# Analog_Sensors_Sheet.net
KiCad netlist of a schematic drawn in Altium Designer
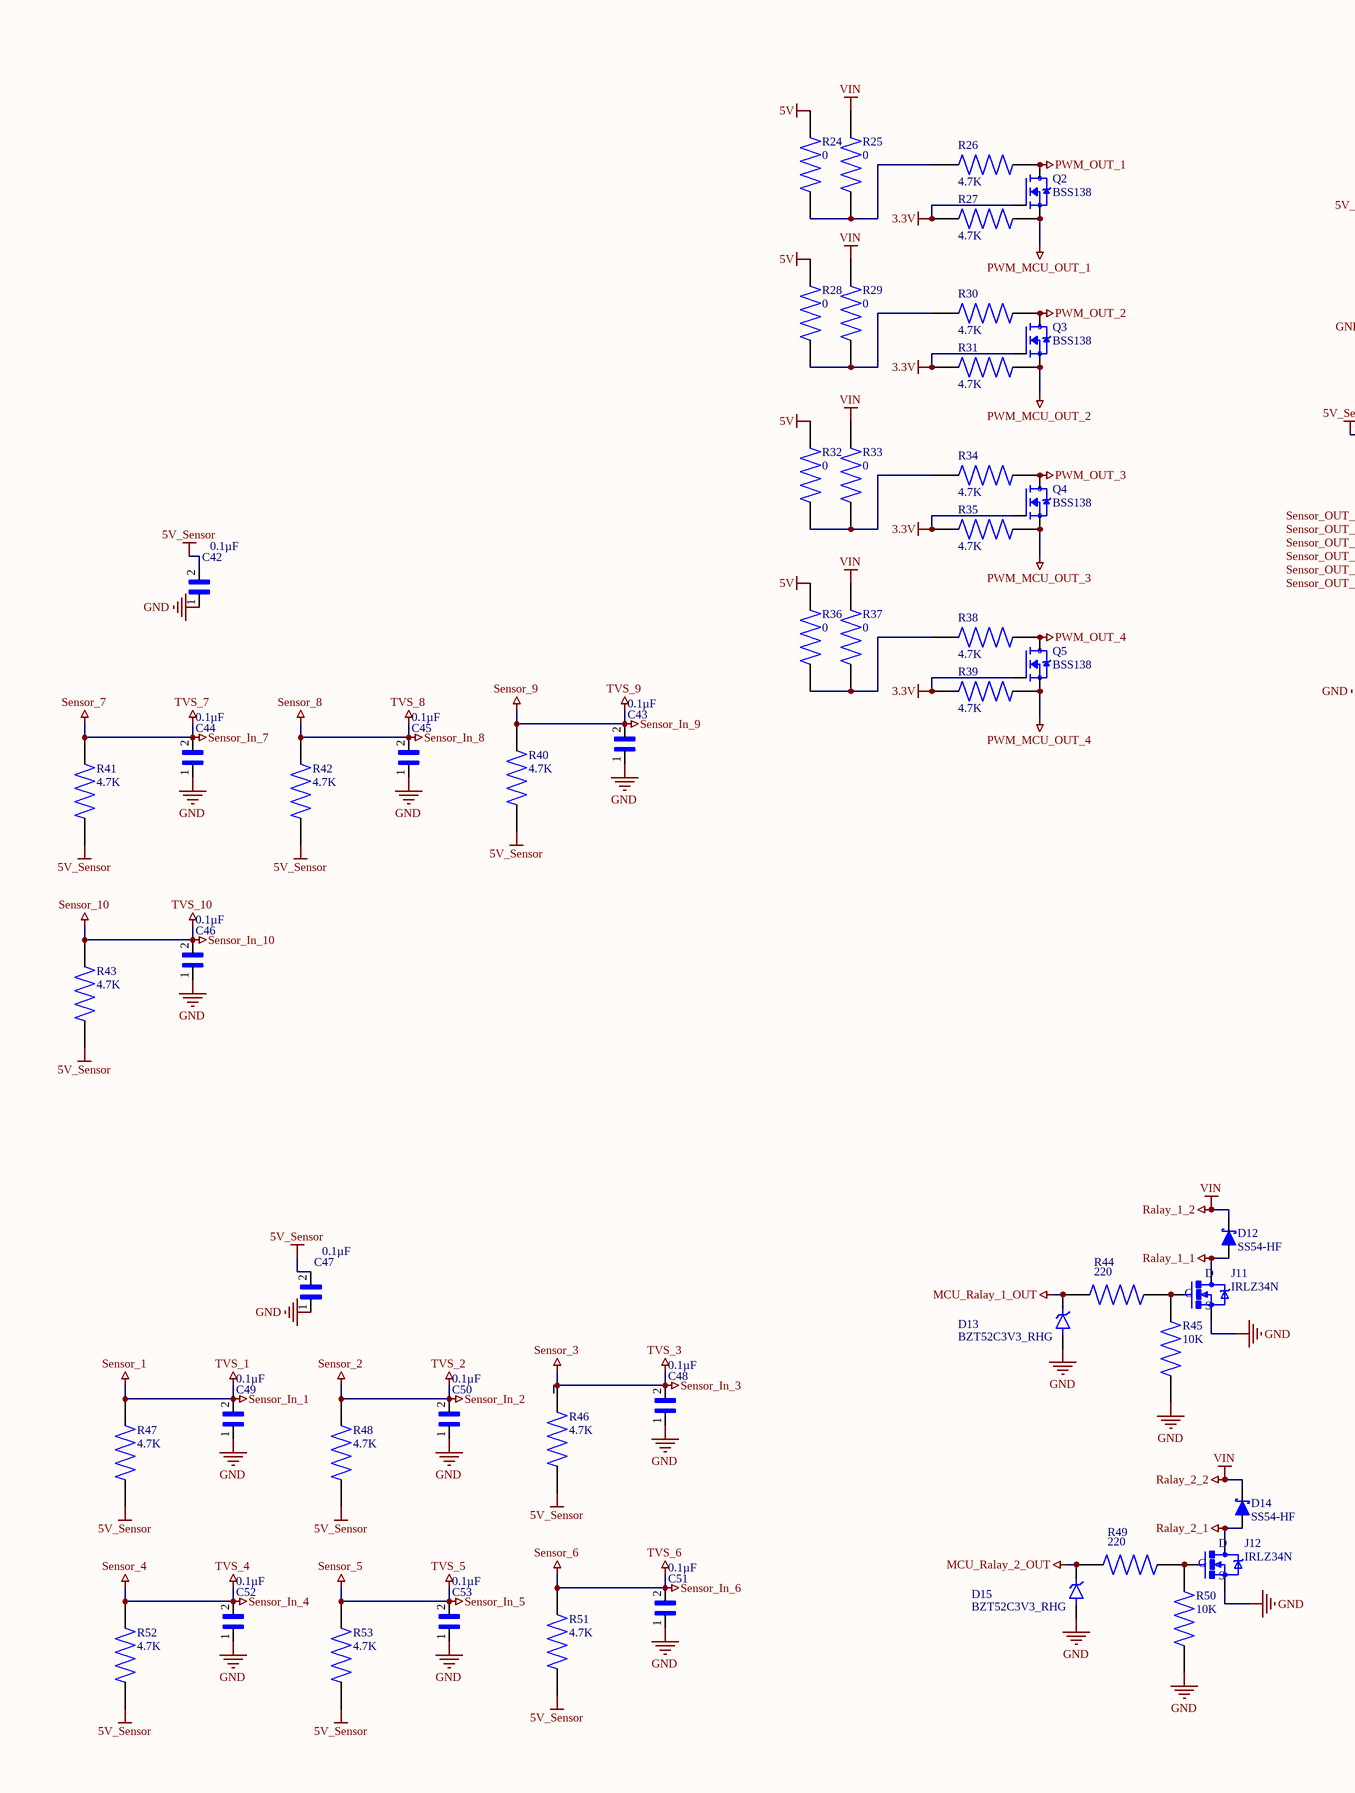
[diagram p0: Analog_Sensors_Sheet.SchDoc, left]
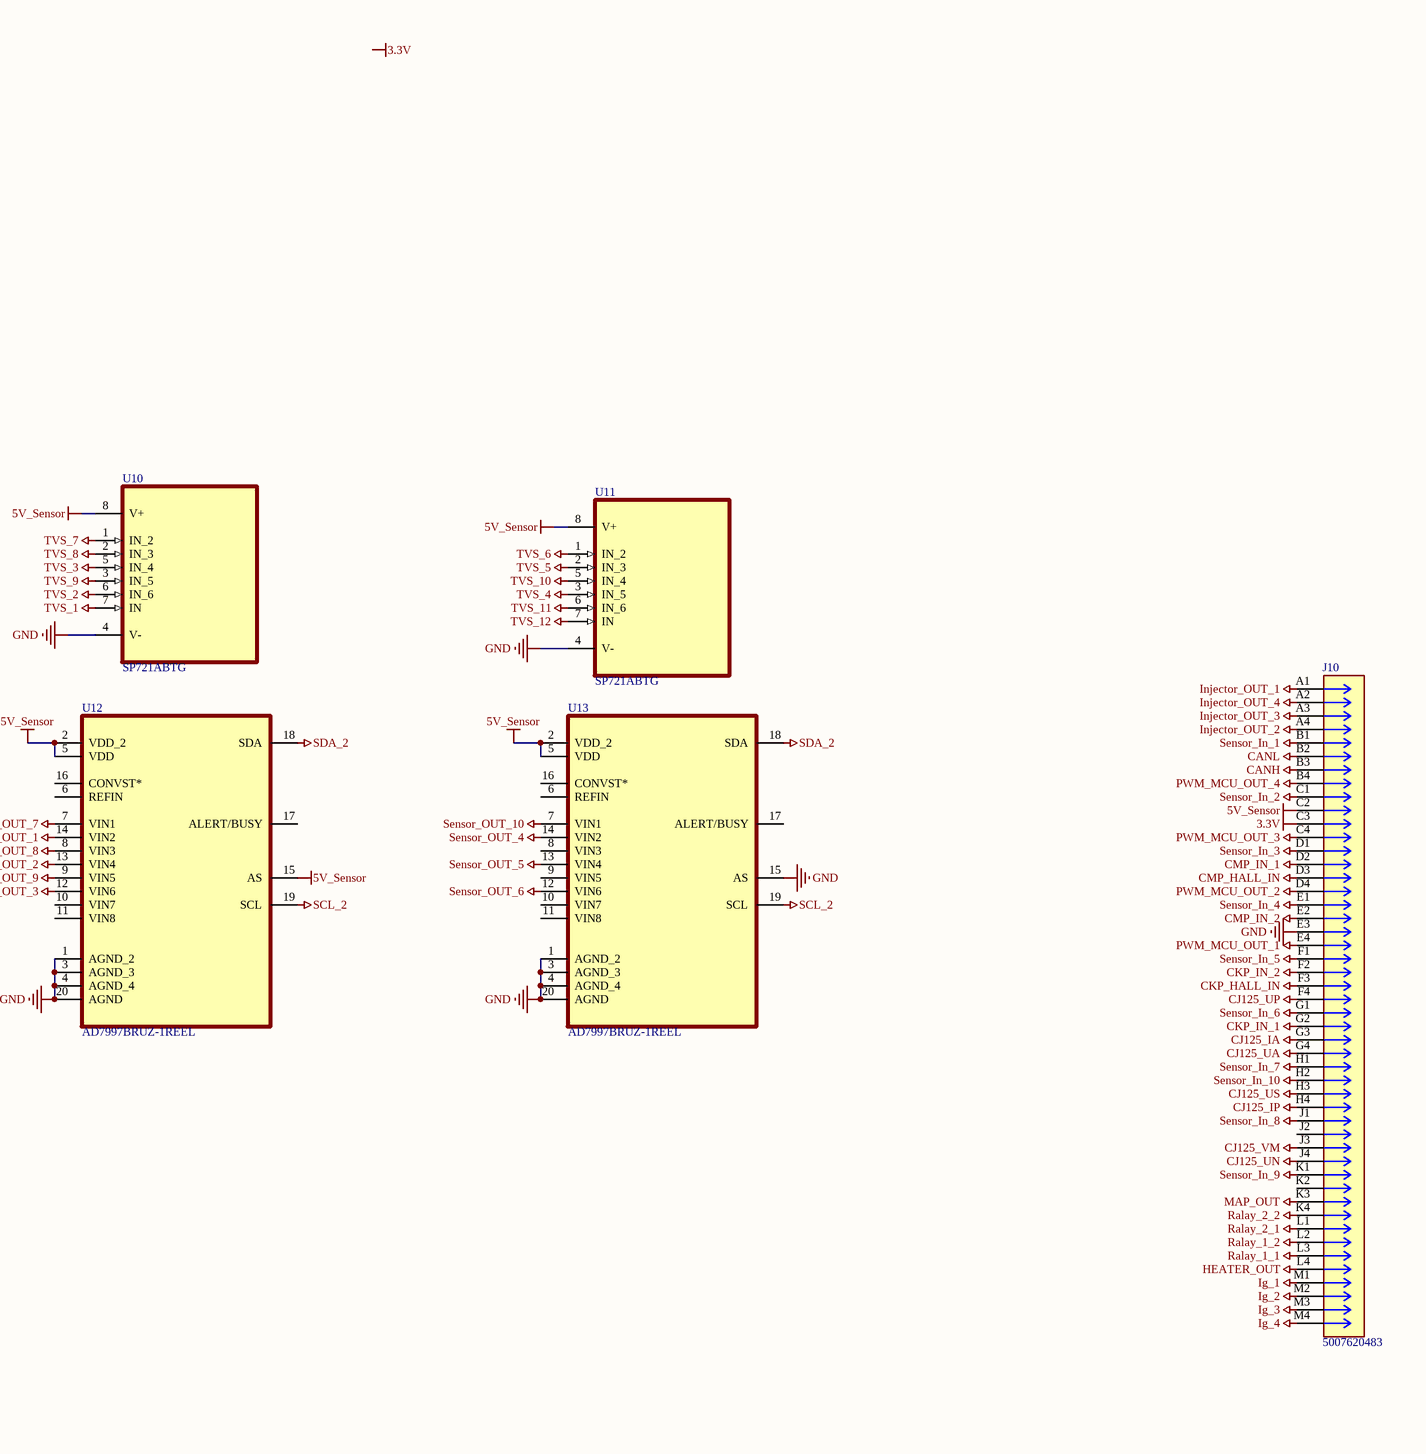
[diagram p1: Analog_Sensors_Sheet.SchDoc, right]

(export (version "E")
  (design (tool "Eeschema 10.0.6"))
  (components
    (comp (ref "C42")
      (value "0.1µF")
      (footprint "CAPC1608X90N")
      (description "Multilayer Ceramic Capacitors MLCC - SMD/SMT")
      (fields (field (name "MP") "06035C104MAZ2A"))
      (libsource (lib "06035C104MAZ2A") (part "06035C104MAZ2A"))
    )
    (comp (ref "C43")
      (value "0.1µF")
      (footprint "CAPC1608X90N")
      (description "Multilayer Ceramic Capacitors MLCC - SMD/SMT")
      (fields (field (name "MP") "06035C104MAZ2A"))
      (libsource (lib "06035C104MAZ2A") (part "06035C104MAZ2A"))
    )
    (comp (ref "C44")
      (value "0.1µF")
      (footprint "CAPC1608X90N")
      (description "Multilayer Ceramic Capacitors MLCC - SMD/SMT")
      (fields (field (name "MP") "06035C104MAZ2A"))
      (libsource (lib "06035C104MAZ2A") (part "06035C104MAZ2A"))
    )
    (comp (ref "C45")
      (value "0.1µF")
      (footprint "CAPC1608X90N")
      (description "Multilayer Ceramic Capacitors MLCC - SMD/SMT")
      (fields (field (name "MP") "06035C104MAZ2A"))
      (libsource (lib "06035C104MAZ2A") (part "06035C104MAZ2A"))
    )
    (comp (ref "C46")
      (value "0.1µF")
      (footprint "CAPC1608X90N")
      (description "Multilayer Ceramic Capacitors MLCC - SMD/SMT")
      (fields (field (name "MP") "06035C104MAZ2A"))
      (libsource (lib "06035C104MAZ2A") (part "06035C104MAZ2A"))
    )
    (comp (ref "C47")
      (value "0.1µF")
      (footprint "CAPC1608X90N")
      (description "Multilayer Ceramic Capacitors MLCC - SMD/SMT")
      (fields (field (name "MP") "06035C104MAZ2A"))
      (libsource (lib "06035C104MAZ2A") (part "06035C104MAZ2A"))
    )
    (comp (ref "C48")
      (value "0.1µF")
      (footprint "CAPC1608X90N")
      (description "Multilayer Ceramic Capacitors MLCC - SMD/SMT")
      (fields (field (name "MP") "06035C104MAZ2A"))
      (libsource (lib "06035C104MAZ2A") (part "06035C104MAZ2A"))
    )
    (comp (ref "C49")
      (value "0.1µF")
      (footprint "CAPC1608X90N")
      (description "Multilayer Ceramic Capacitors MLCC - SMD/SMT")
      (fields (field (name "MP") "06035C104MAZ2A"))
      (libsource (lib "06035C104MAZ2A") (part "06035C104MAZ2A"))
    )
    (comp (ref "C50")
      (value "0.1µF")
      (footprint "CAPC1608X90N")
      (description "Multilayer Ceramic Capacitors MLCC - SMD/SMT")
      (fields (field (name "MP") "06035C104MAZ2A"))
      (libsource (lib "06035C104MAZ2A") (part "06035C104MAZ2A"))
    )
    (comp (ref "C51")
      (value "0.1µF")
      (footprint "CAPC1608X90N")
      (description "Multilayer Ceramic Capacitors MLCC - SMD/SMT")
      (fields (field (name "MP") "06035C104MAZ2A"))
      (libsource (lib "06035C104MAZ2A") (part "06035C104MAZ2A"))
    )
    (comp (ref "C52")
      (value "0.1µF")
      (footprint "CAPC1608X90N")
      (description "Multilayer Ceramic Capacitors MLCC - SMD/SMT")
      (fields (field (name "MP") "06035C104MAZ2A"))
      (libsource (lib "06035C104MAZ2A") (part "06035C104MAZ2A"))
    )
    (comp (ref "C53")
      (value "0.1µF")
      (footprint "CAPC1608X90N")
      (description "Multilayer Ceramic Capacitors MLCC - SMD/SMT")
      (fields (field (name "MP") "06035C104MAZ2A"))
      (libsource (lib "06035C104MAZ2A") (part "06035C104MAZ2A"))
    )
    (comp (ref "D12")
      (value "SS54-HF")
      (footprint "DIOM5025X220N")
      (description "Diode Schottky 40 V 5A Surface Mount DO-214AC (SMA)")
      (fields (field (name "MF") "Comchip Technology"))
      (libsource (lib "SS54-HF") (part "SS54-HF"))
    )
    (comp (ref "D13")
      (value "BZT52C3V3_RHG")
      (footprint "DIO_BZT52C3V3_RHG")
      (libsource (lib "BZT52C3V3_RHG") (part "BZT52C3V3_RHG"))
    )
    (comp (ref "D14")
      (value "SS54-HF")
      (footprint "DIOM5025X220N")
      (description "Diode Schottky 40 V 5A Surface Mount DO-214AC (SMA)")
      (fields (field (name "MF") "Comchip Technology"))
      (libsource (lib "SS54-HF") (part "SS54-HF"))
    )
    (comp (ref "D15")
      (value "BZT52C3V3_RHG")
      (footprint "DIO_BZT52C3V3_RHG")
      (libsource (lib "BZT52C3V3_RHG") (part "BZT52C3V3_RHG"))
    )
    (comp (ref "J10")
      (value "5007620483")
      (footprint "CONN_SD-500762-001_MOL")
      (libsource (lib "5007620483") (part "5007620483"))
    )
    (comp (ref "J11")
      (value "IRLZ34N")
      (footprint "TO-220(2)")
      (description "N-Channel 55 V 30A (Tc) 3.8W (Ta), 68W (Tc) Surface Mount D2PAK")
      (fields (field (name "MF") "Infineon"))
      (libsource (lib "IRLZ34N") (part "IRLZ34N"))
    )
    (comp (ref "J12")
      (value "IRLZ34N")
      (footprint "TO-220(2)")
      (description "N-Channel 55 V 30A (Tc) 3.8W (Ta), 68W (Tc) Surface Mount D2PAK")
      (fields (field (name "MF") "Infineon"))
      (libsource (lib "IRLZ34N") (part "IRLZ34N"))
    )
    (comp (ref "Q2")
      (value "BSS138")
      (footprint "SOT95P240X111-3N")
      (description "N-Channel 50 V 220mA (Ta) 350mW (Ta) Surface Mount SOT-23-3")
      (fields (field (name "MF") "onsemi"))
      (libsource (lib "BSS138") (part "BSS138"))
    )
    (comp (ref "Q3")
      (value "BSS138")
      (footprint "SOT95P240X111-3N")
      (description "N-Channel 50 V 220mA (Ta) 350mW (Ta) Surface Mount SOT-23-3")
      (fields (field (name "MF") "onsemi"))
      (libsource (lib "BSS138") (part "BSS138"))
    )
    (comp (ref "Q4")
      (value "BSS138")
      (footprint "SOT95P240X111-3N")
      (description "N-Channel 50 V 220mA (Ta) 350mW (Ta) Surface Mount SOT-23-3")
      (fields (field (name "MF") "onsemi"))
      (libsource (lib "BSS138") (part "BSS138"))
    )
    (comp (ref "Q5")
      (value "BSS138")
      (footprint "SOT95P240X111-3N")
      (description "N-Channel 50 V 220mA (Ta) 350mW (Ta) Surface Mount SOT-23-3")
      (fields (field (name "MF") "onsemi"))
      (libsource (lib "BSS138") (part "BSS138"))
    )
    (comp (ref "R24")
      (value "0")
      (footprint "RESC3116X65N")
      (description "4.7 kOhms Â±1% 0.25W, 1/4W Chip Resistor 1206 (3216 Metric) Moisture Resistant Thick Film")
      (fields (field (name "MF") "Yageo") (field (name "MP") "RC1206FR-074K7L"))
      (libsource (lib "RC1206FR-074K7L") (part "RC1206FR-074K7L"))
    )
    (comp (ref "R25")
      (value "0")
      (footprint "RESC3116X65N")
      (description "4.7 kOhms Â±1% 0.25W, 1/4W Chip Resistor 1206 (3216 Metric) Moisture Resistant Thick Film")
      (fields (field (name "MF") "Yageo") (field (name "MP") "RC1206FR-074K7L"))
      (libsource (lib "RC1206FR-074K7L") (part "RC1206FR-074K7L"))
    )
    (comp (ref "R26")
      (value "4.7K")
      (footprint "RESC3116X65N")
      (description "4.7 kOhms Â±1% 0.25W, 1/4W Chip Resistor 1206 (3216 Metric) Moisture Resistant Thick Film")
      (fields (field (name "MF") "Yageo") (field (name "MP") "RC1206FR-074K7L"))
      (libsource (lib "RC1206FR-074K7L") (part "RC1206FR-074K7L"))
    )
    (comp (ref "R27")
      (value "4.7K")
      (footprint "RESC3116X65N")
      (description "4.7 kOhms Â±1% 0.25W, 1/4W Chip Resistor 1206 (3216 Metric) Moisture Resistant Thick Film")
      (fields (field (name "MF") "Yageo") (field (name "MP") "RC1206FR-074K7L"))
      (libsource (lib "RC1206FR-074K7L") (part "RC1206FR-074K7L"))
    )
    (comp (ref "R28")
      (value "0")
      (footprint "RESC3116X65N")
      (description "4.7 kOhms Â±1% 0.25W, 1/4W Chip Resistor 1206 (3216 Metric) Moisture Resistant Thick Film")
      (fields (field (name "MF") "Yageo") (field (name "MP") "RC1206FR-074K7L"))
      (libsource (lib "RC1206FR-074K7L") (part "RC1206FR-074K7L"))
    )
    (comp (ref "R29")
      (value "0")
      (footprint "RESC3116X65N")
      (description "4.7 kOhms Â±1% 0.25W, 1/4W Chip Resistor 1206 (3216 Metric) Moisture Resistant Thick Film")
      (fields (field (name "MF") "Yageo") (field (name "MP") "RC1206FR-074K7L"))
      (libsource (lib "RC1206FR-074K7L") (part "RC1206FR-074K7L"))
    )
    (comp (ref "R30")
      (value "4.7K")
      (footprint "RESC3116X65N")
      (description "4.7 kOhms Â±1% 0.25W, 1/4W Chip Resistor 1206 (3216 Metric) Moisture Resistant Thick Film")
      (fields (field (name "MF") "Yageo") (field (name "MP") "RC1206FR-074K7L"))
      (libsource (lib "RC1206FR-074K7L") (part "RC1206FR-074K7L"))
    )
    (comp (ref "R31")
      (value "4.7K")
      (footprint "RESC3116X65N")
      (description "4.7 kOhms Â±1% 0.25W, 1/4W Chip Resistor 1206 (3216 Metric) Moisture Resistant Thick Film")
      (fields (field (name "MF") "Yageo") (field (name "MP") "RC1206FR-074K7L"))
      (libsource (lib "RC1206FR-074K7L") (part "RC1206FR-074K7L"))
    )
    (comp (ref "R32")
      (value "0")
      (footprint "RESC3116X65N")
      (description "4.7 kOhms Â±1% 0.25W, 1/4W Chip Resistor 1206 (3216 Metric) Moisture Resistant Thick Film")
      (fields (field (name "MF") "Yageo") (field (name "MP") "RC1206FR-074K7L"))
      (libsource (lib "RC1206FR-074K7L") (part "RC1206FR-074K7L"))
    )
    (comp (ref "R33")
      (value "0")
      (footprint "RESC3116X65N")
      (description "4.7 kOhms Â±1% 0.25W, 1/4W Chip Resistor 1206 (3216 Metric) Moisture Resistant Thick Film")
      (fields (field (name "MF") "Yageo") (field (name "MP") "RC1206FR-074K7L"))
      (libsource (lib "RC1206FR-074K7L") (part "RC1206FR-074K7L"))
    )
    (comp (ref "R34")
      (value "4.7K")
      (footprint "RESC3116X65N")
      (description "4.7 kOhms Â±1% 0.25W, 1/4W Chip Resistor 1206 (3216 Metric) Moisture Resistant Thick Film")
      (fields (field (name "MF") "Yageo") (field (name "MP") "RC1206FR-074K7L"))
      (libsource (lib "RC1206FR-074K7L") (part "RC1206FR-074K7L"))
    )
    (comp (ref "R35")
      (value "4.7K")
      (footprint "RESC3116X65N")
      (description "4.7 kOhms Â±1% 0.25W, 1/4W Chip Resistor 1206 (3216 Metric) Moisture Resistant Thick Film")
      (fields (field (name "MF") "Yageo") (field (name "MP") "RC1206FR-074K7L"))
      (libsource (lib "RC1206FR-074K7L") (part "RC1206FR-074K7L"))
    )
    (comp (ref "R36")
      (value "0")
      (footprint "RESC3116X65N")
      (description "4.7 kOhms Â±1% 0.25W, 1/4W Chip Resistor 1206 (3216 Metric) Moisture Resistant Thick Film")
      (fields (field (name "MF") "Yageo") (field (name "MP") "RC1206FR-074K7L"))
      (libsource (lib "RC1206FR-074K7L") (part "RC1206FR-074K7L"))
    )
    (comp (ref "R37")
      (value "0")
      (footprint "RESC3116X65N")
      (description "4.7 kOhms Â±1% 0.25W, 1/4W Chip Resistor 1206 (3216 Metric) Moisture Resistant Thick Film")
      (fields (field (name "MF") "Yageo") (field (name "MP") "RC1206FR-074K7L"))
      (libsource (lib "RC1206FR-074K7L") (part "RC1206FR-074K7L"))
    )
    (comp (ref "R38")
      (value "4.7K")
      (footprint "RESC3116X65N")
      (description "4.7 kOhms Â±1% 0.25W, 1/4W Chip Resistor 1206 (3216 Metric) Moisture Resistant Thick Film")
      (fields (field (name "MF") "Yageo") (field (name "MP") "RC1206FR-074K7L"))
      (libsource (lib "RC1206FR-074K7L") (part "RC1206FR-074K7L"))
    )
    (comp (ref "R39")
      (value "4.7K")
      (footprint "RESC3116X65N")
      (description "4.7 kOhms Â±1% 0.25W, 1/4W Chip Resistor 1206 (3216 Metric) Moisture Resistant Thick Film")
      (fields (field (name "MF") "Yageo") (field (name "MP") "RC1206FR-074K7L"))
      (libsource (lib "RC1206FR-074K7L") (part "RC1206FR-074K7L"))
    )
    (comp (ref "R40")
      (value "4.7K")
      (footprint "RESC3116X65N")
      (description "4.7 kOhms Â±1% 0.25W, 1/4W Chip Resistor 1206 (3216 Metric) Moisture Resistant Thick Film")
      (fields (field (name "MF") "Yageo") (field (name "MP") "RC1206FR-074K7L"))
      (libsource (lib "RC1206FR-074K7L") (part "RC1206FR-074K7L"))
    )
    (comp (ref "R41")
      (value "4.7K")
      (footprint "RESC3116X65N")
      (description "4.7 kOhms Â±1% 0.25W, 1/4W Chip Resistor 1206 (3216 Metric) Moisture Resistant Thick Film")
      (fields (field (name "MF") "Yageo") (field (name "MP") "RC1206FR-074K7L"))
      (libsource (lib "RC1206FR-074K7L") (part "RC1206FR-074K7L"))
    )
    (comp (ref "R42")
      (value "4.7K")
      (footprint "RESC3116X65N")
      (description "4.7 kOhms Â±1% 0.25W, 1/4W Chip Resistor 1206 (3216 Metric) Moisture Resistant Thick Film")
      (fields (field (name "MF") "Yageo") (field (name "MP") "RC1206FR-074K7L"))
      (libsource (lib "RC1206FR-074K7L") (part "RC1206FR-074K7L"))
    )
    (comp (ref "R43")
      (value "4.7K")
      (footprint "RESC3116X65N")
      (description "4.7 kOhms Â±1% 0.25W, 1/4W Chip Resistor 1206 (3216 Metric) Moisture Resistant Thick Film")
      (fields (field (name "MF") "Yageo") (field (name "MP") "RC1206FR-074K7L"))
      (libsource (lib "RC1206FR-074K7L") (part "RC1206FR-074K7L"))
    )
    (comp (ref "R44")
      (value "220")
      (footprint "RESC3116X65N")
      (fields (field (name "MP") "AA1206JR-07470RL"))
      (libsource (lib "AA1206JR-07470RL") (part "AA1206JR-07470RL"))
    )
    (comp (ref "R45")
      (value "10K")
      (footprint "RESC3116X65N")
      (fields (field (name "MP") "AA1206JR-07470RL"))
      (libsource (lib "AA1206JR-07470RL") (part "AA1206JR-07470RL"))
    )
    (comp (ref "R46")
      (value "4.7K")
      (footprint "RESC3116X65N")
      (description "4.7 kOhms Â±1% 0.25W, 1/4W Chip Resistor 1206 (3216 Metric) Moisture Resistant Thick Film")
      (fields (field (name "MF") "Yageo") (field (name "MP") "RC1206FR-074K7L"))
      (libsource (lib "RC1206FR-074K7L") (part "RC1206FR-074K7L"))
    )
    (comp (ref "R47")
      (value "4.7K")
      (footprint "RESC3116X65N")
      (description "4.7 kOhms Â±1% 0.25W, 1/4W Chip Resistor 1206 (3216 Metric) Moisture Resistant Thick Film")
      (fields (field (name "MF") "Yageo") (field (name "MP") "RC1206FR-074K7L"))
      (libsource (lib "RC1206FR-074K7L") (part "RC1206FR-074K7L"))
    )
    (comp (ref "R48")
      (value "4.7K")
      (footprint "RESC3116X65N")
      (description "4.7 kOhms Â±1% 0.25W, 1/4W Chip Resistor 1206 (3216 Metric) Moisture Resistant Thick Film")
      (fields (field (name "MF") "Yageo") (field (name "MP") "RC1206FR-074K7L"))
      (libsource (lib "RC1206FR-074K7L") (part "RC1206FR-074K7L"))
    )
    (comp (ref "R49")
      (value "220")
      (footprint "RESC3116X65N")
      (fields (field (name "MP") "AA1206JR-07470RL"))
      (libsource (lib "AA1206JR-07470RL") (part "AA1206JR-07470RL"))
    )
    (comp (ref "R50")
      (value "10K")
      (footprint "RESC3116X65N")
      (fields (field (name "MP") "AA1206JR-07470RL"))
      (libsource (lib "AA1206JR-07470RL") (part "AA1206JR-07470RL"))
    )
    (comp (ref "R51")
      (value "4.7K")
      (footprint "RESC3116X65N")
      (description "4.7 kOhms Â±1% 0.25W, 1/4W Chip Resistor 1206 (3216 Metric) Moisture Resistant Thick Film")
      (fields (field (name "MF") "Yageo") (field (name "MP") "RC1206FR-074K7L"))
      (libsource (lib "RC1206FR-074K7L") (part "RC1206FR-074K7L"))
    )
    (comp (ref "R52")
      (value "4.7K")
      (footprint "RESC3116X65N")
      (description "4.7 kOhms Â±1% 0.25W, 1/4W Chip Resistor 1206 (3216 Metric) Moisture Resistant Thick Film")
      (fields (field (name "MF") "Yageo") (field (name "MP") "RC1206FR-074K7L"))
      (libsource (lib "RC1206FR-074K7L") (part "RC1206FR-074K7L"))
    )
    (comp (ref "R53")
      (value "4.7K")
      (footprint "RESC3116X65N")
      (description "4.7 kOhms Â±1% 0.25W, 1/4W Chip Resistor 1206 (3216 Metric) Moisture Resistant Thick Film")
      (fields (field (name "MF") "Yageo") (field (name "MP") "RC1206FR-074K7L"))
      (libsource (lib "RC1206FR-074K7L") (part "RC1206FR-074K7L"))
    )
    (comp (ref "U10")
      (value "SP721ABTG")
      (footprint "SOIC127P600X175-8N")
      (description "TVS Diode Arrays")
      (libsource (lib "SP721ABTG") (part "SP721ABTG"))
    )
    (comp (ref "U11")
      (value "SP721ABTG")
      (footprint "SOIC127P600X175-8N")
      (description "TVS Diode Arrays")
      (libsource (lib "SP721ABTG") (part "SP721ABTG"))
    )
    (comp (ref "U12")
      (value "AD7997BRUZ-1REEL")
      (footprint "SOP65P640X120-20N")
      (fields (field (name "MF") "Analog Devices") (field (name "MP") "AD7997BRUZ1"))
      (libsource (lib "AD7997BRUZ-1REEL") (part "AD7997BRUZ-1REEL"))
    )
    (comp (ref "U13")
      (value "AD7997BRUZ-1REEL")
      (footprint "SOP65P640X120-20N")
      (fields (field (name "MF") "Analog Devices") (field (name "MP") "AD7997BRUZ1"))
      (libsource (lib "AD7997BRUZ-1REEL") (part "AD7997BRUZ-1REEL"))
    )
  )
  (nets
    (net (code "1") (name "3.3V") (class "Default")
      (node (ref "J10") (pin "C3") (pinfunction "C3_C3") (pintype "passive"))
      (node (ref "Q2") (pin "1") (pinfunction "G_1") (pintype "passive"))
      (node (ref "Q3") (pin "1") (pinfunction "G_1") (pintype "passive"))
      (node (ref "Q4") (pin "1") (pinfunction "G_1") (pintype "passive"))
      (node (ref "Q5") (pin "1") (pinfunction "G_1") (pintype "passive"))
      (node (ref "R27") (pin "2") (pinfunction "2_2") (pintype "passive"))
      (node (ref "R31") (pin "2") (pinfunction "2_2") (pintype "passive"))
      (node (ref "R35") (pin "2") (pinfunction "2_2") (pintype "passive"))
      (node (ref "R39") (pin "2") (pinfunction "2_2") (pintype "passive"))
    )
    (net (code "2") (name "5V") (class "Default")
      (node (ref "R24") (pin "2") (pinfunction "2_2") (pintype "passive"))
      (node (ref "R28") (pin "2") (pinfunction "2_2") (pintype "passive"))
      (node (ref "R32") (pin "2") (pinfunction "2_2") (pintype "passive"))
      (node (ref "R36") (pin "2") (pinfunction "2_2") (pintype "passive"))
    )
    (net (code "3") (name "5V_Sensor") (class "Default")
      (node (ref "C42") (pin "2") (pinfunction "2_2") (pintype "passive"))
      (node (ref "C47") (pin "2") (pinfunction "2_2") (pintype "passive"))
      (node (ref "J10") (pin "C2") (pinfunction "C2_C2") (pintype "passive"))
      (node (ref "R40") (pin "1") (pinfunction "1_1") (pintype "passive"))
      (node (ref "R41") (pin "1") (pinfunction "1_1") (pintype "passive"))
      (node (ref "R42") (pin "1") (pinfunction "1_1") (pintype "passive"))
      (node (ref "R43") (pin "1") (pinfunction "1_1") (pintype "passive"))
      (node (ref "R46") (pin "1") (pinfunction "1_1") (pintype "passive"))
      (node (ref "R47") (pin "1") (pinfunction "1_1") (pintype "passive"))
      (node (ref "R48") (pin "1") (pinfunction "1_1") (pintype "passive"))
      (node (ref "R51") (pin "1") (pinfunction "1_1") (pintype "passive"))
      (node (ref "R52") (pin "1") (pinfunction "1_1") (pintype "passive"))
      (node (ref "R53") (pin "1") (pinfunction "1_1") (pintype "passive"))
      (node (ref "U10") (pin "8") (pinfunction "V+_8") (pintype "power_in"))
      (node (ref "U11") (pin "8") (pinfunction "V+_8") (pintype "power_in"))
      (node (ref "U12") (pin "15") (pinfunction "AS_15") (pintype "passive"))
      (node (ref "U12") (pin "2") (pinfunction "VDD_2_2") (pintype "power_in"))
      (node (ref "U12") (pin "5") (pinfunction "VDD_5") (pintype "power_in"))
      (node (ref "U13") (pin "2") (pinfunction "VDD_2_2") (pintype "power_in"))
      (node (ref "U13") (pin "5") (pinfunction "VDD_5") (pintype "power_in"))
    )
    (net (code "4") (name "CANH") (class "Default")
      (node (ref "J10") (pin "B3") (pinfunction "B3_B3") (pintype "passive"))
    )
    (net (code "5") (name "CANL") (class "Default")
      (node (ref "J10") (pin "B2") (pinfunction "B2_B2") (pintype "passive"))
    )
    (net (code "6") (name "CJ125_IA") (class "Default")
      (node (ref "J10") (pin "G3") (pinfunction "G3_G3") (pintype "passive"))
    )
    (net (code "7") (name "CJ125_IP") (class "Default")
      (node (ref "J10") (pin "H4") (pinfunction "H4_H4") (pintype "passive"))
    )
    (net (code "8") (name "CJ125_UA") (class "Default")
      (node (ref "J10") (pin "G4") (pinfunction "G4_G4") (pintype "passive"))
    )
    (net (code "9") (name "CJ125_UN") (class "Default")
      (node (ref "J10") (pin "J4") (pinfunction "J4_J4") (pintype "passive"))
    )
    (net (code "10") (name "CJ125_UP") (class "Default")
      (node (ref "J10") (pin "F4") (pinfunction "F4_F4") (pintype "passive"))
    )
    (net (code "11") (name "CJ125_US") (class "Default")
      (node (ref "J10") (pin "H3") (pinfunction "H3_H3") (pintype "passive"))
    )
    (net (code "12") (name "CJ125_VM") (class "Default")
      (node (ref "J10") (pin "J3") (pinfunction "J3_J3") (pintype "passive"))
    )
    (net (code "13") (name "CKP_HALL_IN") (class "Default")
      (node (ref "J10") (pin "F3") (pinfunction "F3_F3") (pintype "passive"))
    )
    (net (code "14") (name "CKP_IN_1") (class "Default")
      (node (ref "J10") (pin "G2") (pinfunction "G2_G2") (pintype "passive"))
    )
    (net (code "15") (name "CKP_IN_2") (class "Default")
      (node (ref "J10") (pin "F2") (pinfunction "F2_F2") (pintype "passive"))
    )
    (net (code "16") (name "CMP_HALL_IN") (class "Default")
      (node (ref "J10") (pin "D3") (pinfunction "D3_D3") (pintype "passive"))
    )
    (net (code "17") (name "CMP_IN_1") (class "Default")
      (node (ref "J10") (pin "D2") (pinfunction "D2_D2") (pintype "passive"))
    )
    (net (code "18") (name "CMP_IN_2") (class "Default")
      (node (ref "J10") (pin "E2") (pinfunction "E2_E2") (pintype "passive"))
    )
    (net (code "19") (name "GND") (class "Default")
      (node (ref "C42") (pin "1") (pinfunction "1_1") (pintype "passive"))
      (node (ref "C43") (pin "1") (pinfunction "1_1") (pintype "passive"))
      (node (ref "C44") (pin "1") (pinfunction "1_1") (pintype "passive"))
      (node (ref "C45") (pin "1") (pinfunction "1_1") (pintype "passive"))
      (node (ref "C46") (pin "1") (pinfunction "1_1") (pintype "passive"))
      (node (ref "C47") (pin "1") (pinfunction "1_1") (pintype "passive"))
      (node (ref "C48") (pin "1") (pinfunction "1_1") (pintype "passive"))
      (node (ref "C49") (pin "1") (pinfunction "1_1") (pintype "passive"))
      (node (ref "C50") (pin "1") (pinfunction "1_1") (pintype "passive"))
      (node (ref "C51") (pin "1") (pinfunction "1_1") (pintype "passive"))
      (node (ref "C52") (pin "1") (pinfunction "1_1") (pintype "passive"))
      (node (ref "C53") (pin "1") (pinfunction "1_1") (pintype "passive"))
      (node (ref "D13") (pin "A") (pinfunction "A_A") (pintype "passive"))
      (node (ref "D15") (pin "A") (pinfunction "A_A") (pintype "passive"))
      (node (ref "J10") (pin "E3") (pinfunction "E3_E3") (pintype "passive"))
      (node (ref "J11") (pin "OUT") (pinfunction "S_OUT") (pintype "passive"))
      (node (ref "J12") (pin "OUT") (pinfunction "S_OUT") (pintype "passive"))
      (node (ref "R45") (pin "2") (pinfunction "2_2") (pintype "passive"))
      (node (ref "R50") (pin "2") (pinfunction "2_2") (pintype "passive"))
      (node (ref "U10") (pin "4") (pinfunction "V-_4") (pintype "passive"))
      (node (ref "U11") (pin "4") (pinfunction "V-_4") (pintype "passive"))
      (node (ref "U12") (pin "1") (pinfunction "AGND_2_1") (pintype "passive"))
      (node (ref "U12") (pin "20") (pinfunction "AGND_20") (pintype "passive"))
      (node (ref "U12") (pin "3") (pinfunction "AGND_3_3") (pintype "passive"))
      (node (ref "U12") (pin "4") (pinfunction "AGND_4_4") (pintype "passive"))
      (node (ref "U13") (pin "1") (pinfunction "AGND_2_1") (pintype "passive"))
      (node (ref "U13") (pin "15") (pinfunction "AS_15") (pintype "passive"))
      (node (ref "U13") (pin "20") (pinfunction "AGND_20") (pintype "passive"))
      (node (ref "U13") (pin "3") (pinfunction "AGND_3_3") (pintype "passive"))
      (node (ref "U13") (pin "4") (pinfunction "AGND_4_4") (pintype "passive"))
    )
    (net (code "20") (name "HEATER_OUT") (class "Default")
      (node (ref "J10") (pin "L4") (pinfunction "L4_L4") (pintype "passive"))
    )
    (net (code "21") (name "Ig_1") (class "Default")
      (node (ref "J10") (pin "M1") (pinfunction "M1_M1") (pintype "passive"))
    )
    (net (code "22") (name "Ig_2") (class "Default")
      (node (ref "J10") (pin "M2") (pinfunction "M2_M2") (pintype "passive"))
    )
    (net (code "23") (name "Ig_3") (class "Default")
      (node (ref "J10") (pin "M3") (pinfunction "M3_M3") (pintype "passive"))
    )
    (net (code "24") (name "Ig_4") (class "Default")
      (node (ref "J10") (pin "M4") (pinfunction "M4_M4") (pintype "passive"))
    )
    (net (code "25") (name "Injector_OUT_1") (class "Default")
      (node (ref "J10") (pin "A1") (pinfunction "A1_A1") (pintype "passive"))
    )
    (net (code "26") (name "Injector_OUT_2") (class "Default")
      (node (ref "J10") (pin "A4") (pinfunction "A4_A4") (pintype "passive"))
    )
    (net (code "27") (name "Injector_OUT_3") (class "Default")
      (node (ref "J10") (pin "A3") (pinfunction "A3_A3") (pintype "passive"))
    )
    (net (code "28") (name "Injector_OUT_4") (class "Default")
      (node (ref "J10") (pin "A2") (pinfunction "A2_A2") (pintype "passive"))
    )
    (net (code "29") (name "MAP_OUT") (class "Default")
      (node (ref "J10") (pin "K3") (pinfunction "K3_K3") (pintype "passive"))
    )
    (net (code "30") (name "MCU_Ralay_1_OUT") (class "Default")
      (node (ref "D13") (pin "C") (pinfunction "K_C") (pintype "passive"))
      (node (ref "R44") (pin "1") (pinfunction "1_1") (pintype "passive"))
    )
    (net (code "31") (name "MCU_Ralay_2_OUT") (class "Default")
      (node (ref "D15") (pin "C") (pinfunction "K_C") (pintype "passive"))
      (node (ref "R49") (pin "1") (pinfunction "1_1") (pintype "passive"))
    )
    (net (code "32") (name "Net-(J11-G)") (class "Default")
      (node (ref "J11") (pin "IN") (pinfunction "G_IN") (pintype "passive"))
      (node (ref "R44") (pin "2") (pinfunction "2_2") (pintype "passive"))
      (node (ref "R45") (pin "1") (pinfunction "1_1") (pintype "passive"))
    )
    (net (code "33") (name "Net-(J12-G)") (class "Default")
      (node (ref "J12") (pin "IN") (pinfunction "G_IN") (pintype "passive"))
      (node (ref "R49") (pin "2") (pinfunction "2_2") (pintype "passive"))
      (node (ref "R50") (pin "1") (pinfunction "1_1") (pintype "passive"))
    )
    (net (code "34") (name "Net-(R24-Pad1)") (class "Default")
      (node (ref "R24") (pin "1") (pinfunction "1_1") (pintype "passive"))
      (node (ref "R25") (pin "1") (pinfunction "1_1") (pintype "passive"))
      (node (ref "R26") (pin "2") (pinfunction "2_2") (pintype "passive"))
    )
    (net (code "35") (name "Net-(R28-Pad1)") (class "Default")
      (node (ref "R28") (pin "1") (pinfunction "1_1") (pintype "passive"))
      (node (ref "R29") (pin "1") (pinfunction "1_1") (pintype "passive"))
      (node (ref "R30") (pin "2") (pinfunction "2_2") (pintype "passive"))
    )
    (net (code "36") (name "Net-(R32-Pad1)") (class "Default")
      (node (ref "R32") (pin "1") (pinfunction "1_1") (pintype "passive"))
      (node (ref "R33") (pin "1") (pinfunction "1_1") (pintype "passive"))
      (node (ref "R34") (pin "2") (pinfunction "2_2") (pintype "passive"))
    )
    (net (code "37") (name "Net-(R36-Pad1)") (class "Default")
      (node (ref "R36") (pin "1") (pinfunction "1_1") (pintype "passive"))
      (node (ref "R37") (pin "1") (pinfunction "1_1") (pintype "passive"))
      (node (ref "R38") (pin "2") (pinfunction "2_2") (pintype "passive"))
    )
    (net (code "38") (name "PWM_MCU_OUT_1") (class "Default")
      (node (ref "J10") (pin "E4") (pinfunction "E4_E4") (pintype "passive"))
      (node (ref "Q2") (pin "2") (pinfunction "S_2") (pintype "passive"))
      (node (ref "R27") (pin "1") (pinfunction "1_1") (pintype "passive"))
    )
    (net (code "39") (name "PWM_MCU_OUT_2") (class "Default")
      (node (ref "J10") (pin "D4") (pinfunction "D4_D4") (pintype "passive"))
      (node (ref "Q3") (pin "2") (pinfunction "S_2") (pintype "passive"))
      (node (ref "R31") (pin "1") (pinfunction "1_1") (pintype "passive"))
    )
    (net (code "40") (name "PWM_MCU_OUT_3") (class "Default")
      (node (ref "J10") (pin "C4") (pinfunction "C4_C4") (pintype "passive"))
      (node (ref "Q4") (pin "2") (pinfunction "S_2") (pintype "passive"))
      (node (ref "R35") (pin "1") (pinfunction "1_1") (pintype "passive"))
    )
    (net (code "41") (name "PWM_MCU_OUT_4") (class "Default")
      (node (ref "J10") (pin "B4") (pinfunction "B4_B4") (pintype "passive"))
      (node (ref "Q5") (pin "2") (pinfunction "S_2") (pintype "passive"))
      (node (ref "R39") (pin "1") (pinfunction "1_1") (pintype "passive"))
    )
    (net (code "42") (name "PWM_OUT_1") (class "Default")
      (node (ref "Q2") (pin "3") (pinfunction "D_3") (pintype "passive"))
      (node (ref "R26") (pin "1") (pinfunction "1_1") (pintype "passive"))
    )
    (net (code "43") (name "PWM_OUT_2") (class "Default")
      (node (ref "Q3") (pin "3") (pinfunction "D_3") (pintype "passive"))
      (node (ref "R30") (pin "1") (pinfunction "1_1") (pintype "passive"))
    )
    (net (code "44") (name "PWM_OUT_3") (class "Default")
      (node (ref "Q4") (pin "3") (pinfunction "D_3") (pintype "passive"))
      (node (ref "R34") (pin "1") (pinfunction "1_1") (pintype "passive"))
    )
    (net (code "45") (name "PWM_OUT_4") (class "Default")
      (node (ref "Q5") (pin "3") (pinfunction "D_3") (pintype "passive"))
      (node (ref "R38") (pin "1") (pinfunction "1_1") (pintype "passive"))
    )
    (net (code "46") (name "Ralay_1_1") (class "Default")
      (node (ref "D12") (pin "2") (pinfunction "A_2") (pintype "bidirectional"))
      (node (ref "J10") (pin "L3") (pinfunction "L3_L3") (pintype "passive"))
      (node (ref "J11") (pin "GND") (pinfunction "D_GND") (pintype "passive"))
    )
    (net (code "47") (name "Ralay_1_2") (class "Default")
      (node (ref "D12") (pin "1") (pinfunction "K_1") (pintype "bidirectional"))
      (node (ref "D14") (pin "1") (pinfunction "K_1") (pintype "bidirectional"))
      (node (ref "J10") (pin "K4") (pinfunction "K4_K4") (pintype "passive"))
      (node (ref "J10") (pin "L2") (pinfunction "L2_L2") (pintype "passive"))
      (node (ref "R25") (pin "2") (pinfunction "2_2") (pintype "passive"))
      (node (ref "R29") (pin "2") (pinfunction "2_2") (pintype "passive"))
      (node (ref "R33") (pin "2") (pinfunction "2_2") (pintype "passive"))
      (node (ref "R37") (pin "2") (pinfunction "2_2") (pintype "passive"))
    )
    (net (code "48") (name "Ralay_2_1") (class "Default")
      (node (ref "D14") (pin "2") (pinfunction "A_2") (pintype "bidirectional"))
      (node (ref "J10") (pin "L1") (pinfunction "L1_L1") (pintype "passive"))
      (node (ref "J12") (pin "GND") (pinfunction "D_GND") (pintype "passive"))
    )
    (net (code "49") (name "SCL_2") (class "Default")
      (node (ref "U12") (pin "19") (pinfunction "SCL_19") (pintype "passive"))
      (node (ref "U13") (pin "19") (pinfunction "SCL_19") (pintype "passive"))
    )
    (net (code "50") (name "SDA_2") (class "Default")
      (node (ref "U12") (pin "18") (pinfunction "SDA_18") (pintype "passive"))
      (node (ref "U13") (pin "18") (pinfunction "SDA_18") (pintype "passive"))
    )
    (net (code "51") (name "Sensor_1") (class "Default")
      (node (ref "C49") (pin "2") (pinfunction "2_2") (pintype "passive"))
      (node (ref "J10") (pin "B1") (pinfunction "B1_B1") (pintype "passive"))
      (node (ref "R47") (pin "2") (pinfunction "2_2") (pintype "passive"))
      (node (ref "U10") (pin "7") (pinfunction "IN_7") (pintype "input"))
    )
    (net (code "52") (name "Sensor_2") (class "Default")
      (node (ref "C50") (pin "2") (pinfunction "2_2") (pintype "passive"))
      (node (ref "J10") (pin "C1") (pinfunction "C1_C1") (pintype "passive"))
      (node (ref "R48") (pin "2") (pinfunction "2_2") (pintype "passive"))
      (node (ref "U10") (pin "6") (pinfunction "IN_6_6") (pintype "input"))
    )
    (net (code "53") (name "Sensor_3") (class "Default")
      (node (ref "C48") (pin "2") (pinfunction "2_2") (pintype "passive"))
      (node (ref "J10") (pin "D1") (pinfunction "D1_D1") (pintype "passive"))
      (node (ref "R46") (pin "2") (pinfunction "2_2") (pintype "passive"))
      (node (ref "U10") (pin "5") (pinfunction "IN_4_5") (pintype "input"))
    )
    (net (code "54") (name "Sensor_4") (class "Default")
      (node (ref "C52") (pin "2") (pinfunction "2_2") (pintype "passive"))
      (node (ref "J10") (pin "E1") (pinfunction "E1_E1") (pintype "passive"))
      (node (ref "R52") (pin "2") (pinfunction "2_2") (pintype "passive"))
      (node (ref "U11") (pin "3") (pinfunction "IN_5_3") (pintype "input"))
    )
    (net (code "55") (name "Sensor_5") (class "Default")
      (node (ref "C53") (pin "2") (pinfunction "2_2") (pintype "passive"))
      (node (ref "J10") (pin "F1") (pinfunction "F1_F1") (pintype "passive"))
      (node (ref "R53") (pin "2") (pinfunction "2_2") (pintype "passive"))
      (node (ref "U11") (pin "2") (pinfunction "IN_3_2") (pintype "input"))
    )
    (net (code "56") (name "Sensor_6") (class "Default")
      (node (ref "C51") (pin "2") (pinfunction "2_2") (pintype "passive"))
      (node (ref "J10") (pin "G1") (pinfunction "G1_G1") (pintype "passive"))
      (node (ref "R51") (pin "2") (pinfunction "2_2") (pintype "passive"))
      (node (ref "U11") (pin "1") (pinfunction "IN_2_1") (pintype "input"))
    )
    (net (code "57") (name "Sensor_7") (class "Default")
      (node (ref "C44") (pin "2") (pinfunction "2_2") (pintype "passive"))
      (node (ref "J10") (pin "H1") (pinfunction "H1_H1") (pintype "passive"))
      (node (ref "R41") (pin "2") (pinfunction "2_2") (pintype "passive"))
      (node (ref "U10") (pin "1") (pinfunction "IN_2_1") (pintype "input"))
    )
    (net (code "58") (name "Sensor_8") (class "Default")
      (node (ref "C45") (pin "2") (pinfunction "2_2") (pintype "passive"))
      (node (ref "J10") (pin "J1") (pinfunction "J1_J1") (pintype "passive"))
      (node (ref "R42") (pin "2") (pinfunction "2_2") (pintype "passive"))
      (node (ref "U10") (pin "2") (pinfunction "IN_3_2") (pintype "input"))
    )
    (net (code "59") (name "Sensor_9") (class "Default")
      (node (ref "C43") (pin "2") (pinfunction "2_2") (pintype "passive"))
      (node (ref "J10") (pin "K1") (pinfunction "K1_K1") (pintype "passive"))
      (node (ref "R40") (pin "2") (pinfunction "2_2") (pintype "passive"))
      (node (ref "U10") (pin "3") (pinfunction "IN_5_3") (pintype "input"))
    )
    (net (code "60") (name "Sensor_10") (class "Default")
      (node (ref "C46") (pin "2") (pinfunction "2_2") (pintype "passive"))
      (node (ref "J10") (pin "H2") (pinfunction "H2_H2") (pintype "passive"))
      (node (ref "R43") (pin "2") (pinfunction "2_2") (pintype "passive"))
      (node (ref "U11") (pin "5") (pinfunction "IN_4_5") (pintype "input"))
    )
    (net (code "61") (name "Sensor_OUT_1") (class "Default")
      (node (ref "U12") (pin "14") (pinfunction "VIN2_14") (pintype "passive"))
    )
    (net (code "62") (name "Sensor_OUT_2") (class "Default")
      (node (ref "U12") (pin "13") (pinfunction "VIN4_13") (pintype "passive"))
    )
    (net (code "63") (name "Sensor_OUT_3") (class "Default")
      (node (ref "U12") (pin "12") (pinfunction "VIN6_12") (pintype "passive"))
    )
    (net (code "64") (name "Sensor_OUT_4") (class "Default")
      (node (ref "U13") (pin "14") (pinfunction "VIN2_14") (pintype "passive"))
    )
    (net (code "65") (name "Sensor_OUT_5") (class "Default")
      (node (ref "U13") (pin "13") (pinfunction "VIN4_13") (pintype "passive"))
    )
    (net (code "66") (name "Sensor_OUT_6") (class "Default")
      (node (ref "U13") (pin "12") (pinfunction "VIN6_12") (pintype "passive"))
    )
    (net (code "67") (name "Sensor_OUT_7") (class "Default")
      (node (ref "U12") (pin "7") (pinfunction "VIN1_7") (pintype "passive"))
    )
    (net (code "68") (name "Sensor_OUT_8") (class "Default")
      (node (ref "U12") (pin "8") (pinfunction "VIN3_8") (pintype "passive"))
    )
    (net (code "69") (name "Sensor_OUT_9") (class "Default")
      (node (ref "U12") (pin "9") (pinfunction "VIN5_9") (pintype "passive"))
    )
    (net (code "70") (name "Sensor_OUT_10") (class "Default")
      (node (ref "U13") (pin "7") (pinfunction "VIN1_7") (pintype "passive"))
    )
    (net (code "71") (name "TVS_11") (class "Default")
      (node (ref "U11") (pin "6") (pinfunction "IN_6_6") (pintype "input"))
    )
    (net (code "72") (name "TVS_12") (class "Default")
      (node (ref "U11") (pin "7") (pinfunction "IN_7") (pintype "input"))
    )
    (net (code "73") (name "unconnected-(J10-PadJ2)") (class "Default")
      (node (ref "J10") (pin "J2") (pinfunction "J2_J2") (pintype "passive"))
    )
    (net (code "74") (name "unconnected-(J10-PadK2)") (class "Default")
      (node (ref "J10") (pin "K2") (pinfunction "K2_K2") (pintype "passive"))
    )
    (net (code "75") (name "unconnected-(U12-ALERT{slash}BUSY-Pad17)") (class "Default")
      (node (ref "U12") (pin "17") (pinfunction "ALERT/BUSY_17") (pintype "passive"))
    )
    (net (code "76") (name "unconnected-(U12-CONVST*-Pad16)") (class "Default")
      (node (ref "U12") (pin "16") (pinfunction "CONVST*_16") (pintype "passive"))
    )
    (net (code "77") (name "unconnected-(U12-REFIN-Pad6)") (class "Default")
      (node (ref "U12") (pin "6") (pinfunction "REFIN_6") (pintype "passive"))
    )
    (net (code "78") (name "unconnected-(U12-VIN7-Pad10)") (class "Default")
      (node (ref "U12") (pin "10") (pinfunction "VIN7_10") (pintype "passive"))
    )
    (net (code "79") (name "unconnected-(U12-VIN8-Pad11)") (class "Default")
      (node (ref "U12") (pin "11") (pinfunction "VIN8_11") (pintype "passive"))
    )
    (net (code "80") (name "unconnected-(U13-ALERT{slash}BUSY-Pad17)") (class "Default")
      (node (ref "U13") (pin "17") (pinfunction "ALERT/BUSY_17") (pintype "passive"))
    )
    (net (code "81") (name "unconnected-(U13-CONVST*-Pad16)") (class "Default")
      (node (ref "U13") (pin "16") (pinfunction "CONVST*_16") (pintype "passive"))
    )
    (net (code "82") (name "unconnected-(U13-REFIN-Pad6)") (class "Default")
      (node (ref "U13") (pin "6") (pinfunction "REFIN_6") (pintype "passive"))
    )
    (net (code "83") (name "unconnected-(U13-VIN3-Pad8)") (class "Default")
      (node (ref "U13") (pin "8") (pinfunction "VIN3_8") (pintype "passive"))
    )
    (net (code "84") (name "unconnected-(U13-VIN5-Pad9)") (class "Default")
      (node (ref "U13") (pin "9") (pinfunction "VIN5_9") (pintype "passive"))
    )
    (net (code "85") (name "unconnected-(U13-VIN7-Pad10)") (class "Default")
      (node (ref "U13") (pin "10") (pinfunction "VIN7_10") (pintype "passive"))
    )
    (net (code "86") (name "unconnected-(U13-VIN8-Pad11)") (class "Default")
      (node (ref "U13") (pin "11") (pinfunction "VIN8_11") (pintype "passive"))
    )
  )
)
